# Sheet2.net
KiCad netlist of a schematic drawn in Altium Designer
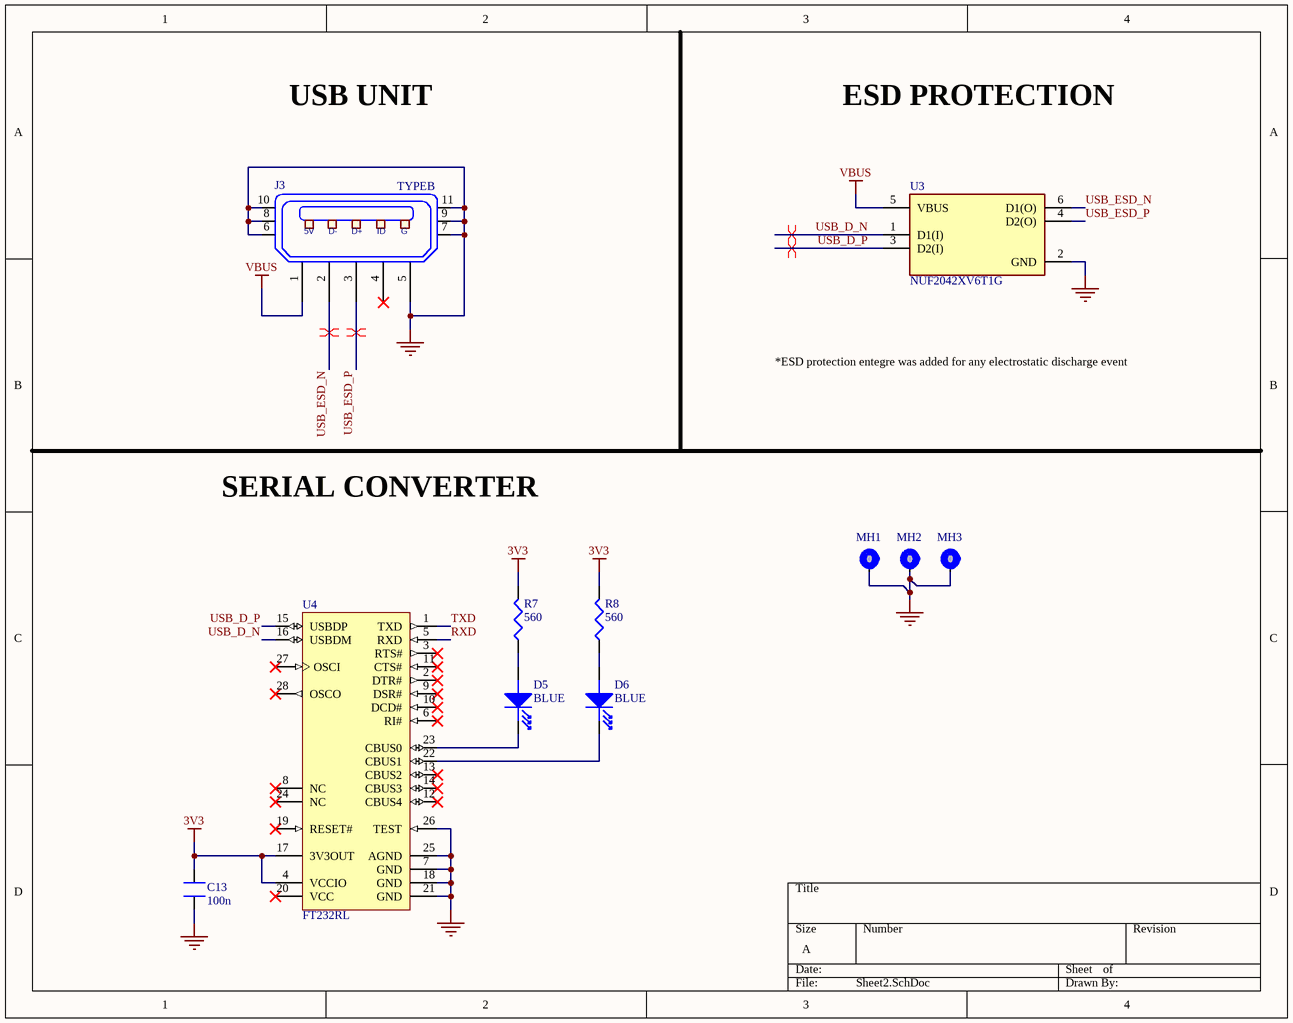
[diagram p0: Sheet2.SchDoc]

(export (version "E")
  (design (tool "Eeschema 10.0.6"))
  (components
    (comp (ref "C13") (value "100n") (footprint "Z0603") (libsource (lib "brain-dll-Sch") (part "C0603")))
    (comp (ref "D5") (value "BLUE") (footprint "LED-0603") (libsource (lib "brain-dll-Sch") (part "L0603")))
    (comp (ref "D6") (value "BLUE") (footprint "LED-0603") (libsource (lib "brain-dll-Sch") (part "L0603")))
    (comp (ref "J3") (value "TYPEB") (footprint "USB-A") (libsource (lib "brain-dll-Sch") (part "USB-TYPEB")))
    (comp (ref "MH1")
      (value "MH_7.4MMC_3.2MMD")
      (footprint "MH_7.4MMC_3.2MMD_NON_COPPER_NPLT")
      (description "Mounting Hole 7.4 mm Diameter (Non Copper), 3.2 mm Drill NPTH")
      (libsource (lib "brain-dll-Sch") (part "MH_7.4MMNC_3.2MMD"))
    )
    (comp (ref "MH2")
      (value "MH_7.4MMC_3.2MMD")
      (footprint "MH_7.4MMC_3.2MMD_NON_COPPER_NPLT")
      (description "Mounting Hole 7.4 mm Diameter (Non Copper), 3.2 mm Drill NPTH")
      (libsource (lib "brain-dll-Sch") (part "MH_7.4MMNC_3.2MMD"))
    )
    (comp (ref "MH3")
      (value "MH_7.4MMC_3.2MMD")
      (footprint "MH_7.4MMC_3.2MMD_NON_COPPER_NPLT")
      (description "Mounting Hole 7.4 mm Diameter (Non Copper), 3.2 mm Drill NPTH")
      (libsource (lib "brain-dll-Sch") (part "MH_7.4MMNC_3.2MMD"))
    )
    (comp (ref "R7") (value "560") (footprint "R0603") (libsource (lib "brain-dll-Sch") (part "R0603")))
    (comp (ref "R8") (value "560") (footprint "R0603") (libsource (lib "brain-dll-Sch") (part "R0603")))
    (comp (ref "U3")
      (value "NUF2042XV6T1G")
      (footprint "FP-463A-MFG")
      (description "FILTER RC(PI) 22 OHM/42PF SMD")
      (libsource (lib "Altium Content Vault") (part "d0bc5b996ea2534323fabd27237c078"))
    )
    (comp (ref "U4")
      (value "FT232RL")
      (footprint "FTDI-SSOP-28_M")
      (description "IC USB FS SERIAL UART 28-SSOP")
      (libsource (lib "Altium Content Vault") (part "FTDI-FT232-SSOP-28"))
    )
  )
  (nets
    (net (code "1") (name "/RXD") (class "Default")
      (node (ref "U4") (pin "5") (pinfunction "RXD_5") (pintype "input"))
    )
    (net (code "2") (name "/TXD") (class "Default")
      (node (ref "U4") (pin "1") (pinfunction "TXD_1") (pintype "output"))
    )
    (net (code "3") (name "/USB_D_N") (class "Default")
      (node (ref "U3") (pin "1") (pinfunction "D1(I)_1") (pintype "passive"))
      (node (ref "U4") (pin "16") (pinfunction "USBDM_16") (pintype "bidirectional"))
    )
    (net (code "4") (name "/USB_D_P") (class "Default")
      (node (ref "U3") (pin "3") (pinfunction "D2(I)_3") (pintype "passive"))
      (node (ref "U4") (pin "15") (pinfunction "USBDP_15") (pintype "bidirectional"))
    )
    (net (code "5") (name "/USB_ESD_N") (class "Default")
      (node (ref "J3") (pin "2") (pinfunction "2_2") (pintype "passive"))
      (node (ref "U3") (pin "6") (pinfunction "D1(O)_6") (pintype "passive"))
    )
    (net (code "6") (name "/USB_ESD_P") (class "Default")
      (node (ref "J3") (pin "3") (pinfunction "3_3") (pintype "passive"))
      (node (ref "U3") (pin "4") (pinfunction "D2(O)_4") (pintype "passive"))
    )
    (net (code "7") (name "3V3") (class "Default")
      (node (ref "C13") (pin "2") (pinfunction "2_2") (pintype "passive"))
      (node (ref "R7") (pin "2") (pinfunction "2_2") (pintype "passive"))
      (node (ref "R8") (pin "2") (pinfunction "2_2") (pintype "passive"))
      (node (ref "U4") (pin "17") (pinfunction "3V3OUT_17") (pintype "power_in"))
      (node (ref "U4") (pin "4") (pinfunction "VCCIO_4") (pintype "power_in"))
    )
    (net (code "8") (name "GND") (class "Default")
      (node (ref "C13") (pin "1") (pinfunction "1_1") (pintype "passive"))
      (node (ref "J3") (pin "10") (pinfunction "10_10") (pintype "passive"))
      (node (ref "J3") (pin "11") (pinfunction "11_11") (pintype "passive"))
      (node (ref "J3") (pin "5") (pinfunction "5_5") (pintype "passive"))
      (node (ref "J3") (pin "6") (pinfunction "6_6") (pintype "passive"))
      (node (ref "J3") (pin "7") (pinfunction "7_7") (pintype "passive"))
      (node (ref "J3") (pin "8") (pinfunction "8_8") (pintype "passive"))
      (node (ref "J3") (pin "9") (pinfunction "9_9") (pintype "passive"))
      (node (ref "MH1") (pin "1") (pinfunction "1_1") (pintype "passive"))
      (node (ref "MH2") (pin "1") (pinfunction "1_1") (pintype "passive"))
      (node (ref "MH3") (pin "1") (pinfunction "1_1") (pintype "passive"))
      (node (ref "U3") (pin "2") (pinfunction "GND_2") (pintype "power_in"))
      (node (ref "U4") (pin "18") (pinfunction "GND_18") (pintype "power_in"))
      (node (ref "U4") (pin "21") (pinfunction "GND_21") (pintype "power_in"))
      (node (ref "U4") (pin "25") (pinfunction "AGND_25") (pintype "power_in"))
      (node (ref "U4") (pin "26") (pinfunction "TEST_26") (pintype "input"))
      (node (ref "U4") (pin "7") (pinfunction "GND_7") (pintype "power_in"))
    )
    (net (code "9") (name "Net-(D5-Anode)") (class "Default")
      (node (ref "D5") (pin "2") (pinfunction "Anode_2") (pintype "passive"))
      (node (ref "R7") (pin "1") (pinfunction "1_1") (pintype "passive"))
    )
    (net (code "10") (name "Net-(D5-Cathode)") (class "Default")
      (node (ref "D5") (pin "1") (pinfunction "Cathode_1") (pintype "passive"))
      (node (ref "U4") (pin "23") (pinfunction "CBUS0_23") (pintype "bidirectional"))
    )
    (net (code "11") (name "Net-(D6-Anode)") (class "Default")
      (node (ref "D6") (pin "2") (pinfunction "Anode_2") (pintype "passive"))
      (node (ref "R8") (pin "1") (pinfunction "1_1") (pintype "passive"))
    )
    (net (code "12") (name "Net-(D6-Cathode)") (class "Default")
      (node (ref "D6") (pin "1") (pinfunction "Cathode_1") (pintype "passive"))
      (node (ref "U4") (pin "22") (pinfunction "CBUS1_22") (pintype "bidirectional"))
    )
    (net (code "13") (name "VBUS") (class "Default")
      (node (ref "J3") (pin "1") (pinfunction "1_1") (pintype "passive"))
      (node (ref "U3") (pin "5") (pinfunction "VBUS_5") (pintype "power_in"))
    )
    (net (code "14") (name "unconnected-(J3-Pad4)") (class "Default")
      (node (ref "J3") (pin "4") (pinfunction "4_4") (pintype "passive+no_connect"))
    )
    (net (code "15") (name "unconnected-(U4-CBUS2-Pad13)") (class "Default")
      (node (ref "U4") (pin "13") (pinfunction "CBUS2_13") (pintype "bidirectional+no_connect"))
    )
    (net (code "16") (name "unconnected-(U4-CBUS3-Pad14)") (class "Default")
      (node (ref "U4") (pin "14") (pinfunction "CBUS3_14") (pintype "bidirectional+no_connect"))
    )
    (net (code "17") (name "unconnected-(U4-CBUS4-Pad12)") (class "Default")
      (node (ref "U4") (pin "12") (pinfunction "CBUS4_12") (pintype "bidirectional+no_connect"))
    )
    (net (code "18") (name "unconnected-(U4-CTS#-Pad11)") (class "Default")
      (node (ref "U4") (pin "11") (pinfunction "CTS#_11") (pintype "input+no_connect"))
    )
    (net (code "19") (name "unconnected-(U4-DCD#-Pad10)") (class "Default")
      (node (ref "U4") (pin "10") (pinfunction "DCD#_10") (pintype "input+no_connect"))
    )
    (net (code "20") (name "unconnected-(U4-DSR#-Pad9)") (class "Default")
      (node (ref "U4") (pin "9") (pinfunction "DSR#_9") (pintype "input+no_connect"))
    )
    (net (code "21") (name "unconnected-(U4-DTR#-Pad2)") (class "Default")
      (node (ref "U4") (pin "2") (pinfunction "DTR#_2") (pintype "output+no_connect"))
    )
    (net (code "22") (name "unconnected-(U4-NC-Pad8)") (class "Default")
      (node (ref "U4") (pin "8") (pinfunction "NC_8") (pintype "passive+no_connect"))
    )
    (net (code "23") (name "unconnected-(U4-NC-Pad24)") (class "Default")
      (node (ref "U4") (pin "24") (pinfunction "NC_24") (pintype "passive+no_connect"))
    )
    (net (code "24") (name "unconnected-(U4-OSCI-Pad27)") (class "Default")
      (node (ref "U4") (pin "27") (pinfunction "OSCI_27") (pintype "input+no_connect"))
    )
    (net (code "25") (name "unconnected-(U4-OSCO-Pad28)") (class "Default")
      (node (ref "U4") (pin "28") (pinfunction "OSCO_28") (pintype "output+no_connect"))
    )
    (net (code "26") (name "unconnected-(U4-RESET#-Pad19)") (class "Default")
      (node (ref "U4") (pin "19") (pinfunction "RESET#_19") (pintype "input+no_connect"))
    )
    (net (code "27") (name "unconnected-(U4-RI#-Pad6)") (class "Default")
      (node (ref "U4") (pin "6") (pinfunction "RI#_6") (pintype "input+no_connect"))
    )
    (net (code "28") (name "unconnected-(U4-RTS#-Pad3)") (class "Default")
      (node (ref "U4") (pin "3") (pinfunction "RTS#_3") (pintype "output+no_connect"))
    )
    (net (code "29") (name "unconnected-(U4-VCC-Pad20)") (class "Default")
      (node (ref "U4") (pin "20") (pinfunction "VCC_20") (pintype "power_in+no_connect"))
    )
  )
)
